# LCD.net
KiCad netlist of a schematic drawn in Altium Designer
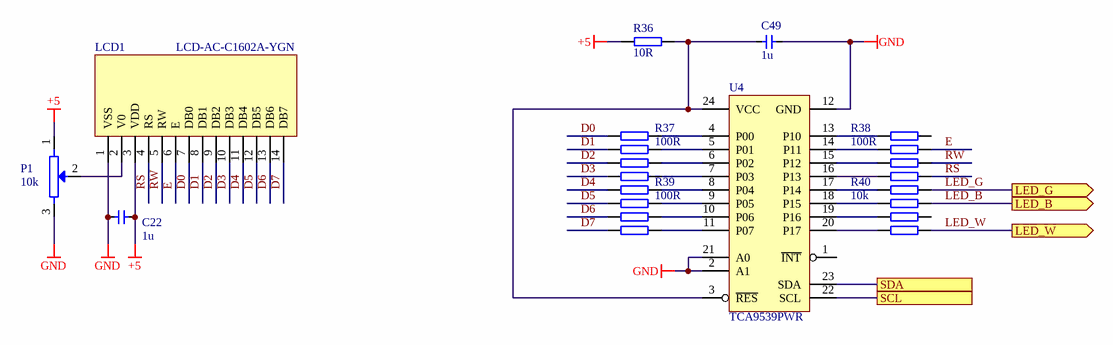
[diagram p0: LCD.SchDoc]

(export (version "E")
  (design (tool "Eeschema 10.0.6"))
  (components
    (comp (ref "C22")
      (value "1u")
      (footprint "C0805")
      (description "C; capacitor")
      (libsource (lib "SONEL_all") (part "C"))
    )
    (comp (ref "C49")
      (value "1u")
      (footprint "C0805")
      (description "C; capacitor")
      (libsource (lib "SONEL_all") (part "C"))
    )
    (comp (ref "LCD1")
      (value "LCD-AC-C1602A-YGN")
      (footprint "LCD-AC-C1602A-YGN")
      (libsource (lib "sch") (part "LCD-AC-C1602A-YGN"))
    )
    (comp (ref "P1")
      (value "10k")
      (footprint "POT67Y")
      (description "R_P")
      (libsource (lib "SONEL_all") (part "POT67Y"))
    )
    (comp (ref "R36")
      (value "10R")
      (footprint "R0805")
      (description "R; resistor")
      (libsource (lib "SONEL_all") (part "R"))
    )
    (comp (ref "R37")
      (value "100R")
      (footprint "YC164")
      (description "R; Drabinka rezystorowa")
      (libsource (lib "SONEL_all") (part "YC164"))
    )
    (comp (ref "R38")
      (value "100R")
      (footprint "YC164")
      (description "R; Drabinka rezystorowa")
      (libsource (lib "SONEL_all") (part "YC164"))
    )
    (comp (ref "R39")
      (value "100R")
      (footprint "YC164")
      (description "R; Drabinka rezystorowa")
      (libsource (lib "SONEL_all") (part "YC164"))
    )
    (comp (ref "R40")
      (value "10k")
      (footprint "YC164")
      (description "R; Drabinka rezystorowa")
      (libsource (lib "SONEL_all") (part "YC164"))
    )
    (comp (ref "U4")
      (value "TCA9539PWR")
      (footprint "PW_R-PDSO-G24")
      (description "I2C 16-BIT port")
      (libsource (lib "SONEL_all") (part "TCA9539PWR"))
    )
  )
  (nets
    (net (code "1") (name "+5") (class "Default")
      (node (ref "C22") (pin "1") (pintype "passive"))
      (node (ref "LCD1") (pin "3") (pinfunction "VDD_3") (pintype "passive"))
      (node (ref "P1") (pin "1") (pinfunction "1_1") (pintype "passive"))
      (node (ref "R36") (pin "2") (pintype "passive"))
    )
    (net (code "2") (name "/D0") (class "Default")
      (node (ref "LCD1") (pin "7") (pinfunction "DB0_7") (pintype "passive"))
      (node (ref "R37") (pin "4") (pintype "passive"))
    )
    (net (code "3") (name "/D1") (class "Default")
      (node (ref "LCD1") (pin "8") (pinfunction "DB1_8") (pintype "passive"))
      (node (ref "R37") (pin "3") (pintype "passive"))
    )
    (net (code "4") (name "/D2") (class "Default")
      (node (ref "LCD1") (pin "9") (pinfunction "DB2_9") (pintype "passive"))
      (node (ref "R37") (pin "2") (pinfunction "2_2") (pintype "passive"))
    )
    (net (code "5") (name "/D3") (class "Default")
      (node (ref "LCD1") (pin "10") (pinfunction "DB3_10") (pintype "passive"))
      (node (ref "R37") (pin "1") (pinfunction "1_1") (pintype "passive"))
    )
    (net (code "6") (name "/D4") (class "Default")
      (node (ref "LCD1") (pin "11") (pinfunction "DB4_11") (pintype "passive"))
      (node (ref "R39") (pin "4") (pintype "passive"))
    )
    (net (code "7") (name "/D5") (class "Default")
      (node (ref "LCD1") (pin "12") (pinfunction "DB5_12") (pintype "passive"))
      (node (ref "R39") (pin "3") (pintype "passive"))
    )
    (net (code "8") (name "/D6") (class "Default")
      (node (ref "LCD1") (pin "13") (pinfunction "DB6_13") (pintype "passive"))
      (node (ref "R39") (pin "2") (pinfunction "2_2") (pintype "passive"))
    )
    (net (code "9") (name "/D7") (class "Default")
      (node (ref "LCD1") (pin "14") (pinfunction "DB7_14") (pintype "passive"))
      (node (ref "R39") (pin "1") (pinfunction "1_1") (pintype "passive"))
    )
    (net (code "10") (name "/E") (class "Default")
      (node (ref "LCD1") (pin "6") (pinfunction "E_6") (pintype "passive"))
      (node (ref "R38") (pin "6") (pintype "passive"))
    )
    (net (code "11") (name "/LED_B") (class "Default") (node (ref "R40") (pin "6") (pintype "passive")))
    (net (code "12") (name "/LED_G") (class "Default") (node (ref "R40") (pin "5") (pintype "passive")))
    (net (code "13") (name "/LED_W") (class "Default") (node (ref "R40") (pin "8") (pintype "passive")))
    (net (code "14") (name "/RS") (class "Default")
      (node (ref "LCD1") (pin "4") (pinfunction "RS_4") (pintype "passive"))
      (node (ref "R38") (pin "8") (pintype "passive"))
    )
    (net (code "15") (name "/RW") (class "Default")
      (node (ref "LCD1") (pin "5") (pinfunction "RW_5") (pintype "passive"))
      (node (ref "R38") (pin "7") (pintype "passive"))
    )
    (net (code "16") (name "/SCL") (class "Default")
      (node (ref "U4") (pin "22") (pinfunction "SCL_22") (pintype "open_collector"))
    )
    (net (code "17") (name "/SDA") (class "Default")
      (node (ref "U4") (pin "23") (pinfunction "SDA_23") (pintype "open_collector"))
    )
    (net (code "18") (name "GND") (class "Default")
      (node (ref "C22") (pin "2") (pintype "passive"))
      (node (ref "C49") (pin "1") (pintype "passive"))
      (node (ref "LCD1") (pin "1") (pinfunction "VSS_1") (pintype "passive"))
      (node (ref "P1") (pin "3") (pinfunction "3_3") (pintype "passive"))
      (node (ref "U4") (pin "12") (pinfunction "GND_12") (pintype "power_in"))
      (node (ref "U4") (pin "2") (pinfunction "A1_2") (pintype "passive"))
      (node (ref "U4") (pin "21") (pinfunction "A0_21") (pintype "passive"))
    )
    (net (code "19") (name "Net-(LCD1-V0)") (class "Default")
      (node (ref "LCD1") (pin "2") (pinfunction "V0_2") (pintype "passive"))
      (node (ref "P1") (pin "2") (pinfunction "2_2") (pintype "passive"))
    )
    (net (code "20") (name "Net-(U4-P00)") (class "Default")
      (node (ref "R37") (pin "5") (pintype "passive"))
      (node (ref "U4") (pin "4") (pinfunction "P00_4") (pintype "passive"))
    )
    (net (code "21") (name "Net-(U4-P01)") (class "Default")
      (node (ref "R37") (pin "6") (pintype "passive"))
      (node (ref "U4") (pin "5") (pinfunction "P01_5") (pintype "passive"))
    )
    (net (code "22") (name "Net-(U4-P02)") (class "Default")
      (node (ref "R37") (pin "7") (pintype "passive"))
      (node (ref "U4") (pin "6") (pinfunction "P02_6") (pintype "passive"))
    )
    (net (code "23") (name "Net-(U4-P03)") (class "Default")
      (node (ref "R37") (pin "8") (pintype "passive"))
      (node (ref "U4") (pin "7") (pinfunction "P03_7") (pintype "passive"))
    )
    (net (code "24") (name "Net-(U4-P04)") (class "Default")
      (node (ref "R39") (pin "5") (pintype "passive"))
      (node (ref "U4") (pin "8") (pinfunction "P04_8") (pintype "passive"))
    )
    (net (code "25") (name "Net-(U4-P05)") (class "Default")
      (node (ref "R39") (pin "6") (pintype "passive"))
      (node (ref "U4") (pin "9") (pinfunction "P05_9") (pintype "passive"))
    )
    (net (code "26") (name "Net-(U4-P06)") (class "Default")
      (node (ref "R39") (pin "7") (pintype "passive"))
      (node (ref "U4") (pin "10") (pinfunction "P06_10") (pintype "passive"))
    )
    (net (code "27") (name "Net-(U4-P07)") (class "Default")
      (node (ref "R39") (pin "8") (pintype "passive"))
      (node (ref "U4") (pin "11") (pinfunction "P07_11") (pintype "passive"))
    )
    (net (code "28") (name "Net-(U4-P10)") (class "Default")
      (node (ref "R38") (pin "4") (pintype "passive"))
      (node (ref "U4") (pin "13") (pinfunction "P10_13") (pintype "passive"))
    )
    (net (code "29") (name "Net-(U4-P11)") (class "Default")
      (node (ref "R38") (pin "3") (pintype "passive"))
      (node (ref "U4") (pin "14") (pinfunction "P11_14") (pintype "passive"))
    )
    (net (code "30") (name "Net-(U4-P12)") (class "Default")
      (node (ref "R38") (pin "2") (pinfunction "2_2") (pintype "passive"))
      (node (ref "U4") (pin "15") (pinfunction "P12_15") (pintype "passive"))
    )
    (net (code "31") (name "Net-(U4-P13)") (class "Default")
      (node (ref "R38") (pin "1") (pinfunction "1_1") (pintype "passive"))
      (node (ref "U4") (pin "16") (pinfunction "P13_16") (pintype "passive"))
    )
    (net (code "32") (name "Net-(U4-P14)") (class "Default")
      (node (ref "R40") (pin "4") (pintype "passive"))
      (node (ref "U4") (pin "17") (pinfunction "P14_17") (pintype "passive"))
    )
    (net (code "33") (name "Net-(U4-P15)") (class "Default")
      (node (ref "R40") (pin "3") (pintype "passive"))
      (node (ref "U4") (pin "18") (pinfunction "P15_18") (pintype "passive"))
    )
    (net (code "34") (name "Net-(U4-P16)") (class "Default")
      (node (ref "R40") (pin "2") (pinfunction "2_2") (pintype "passive"))
      (node (ref "U4") (pin "19") (pinfunction "P16_19") (pintype "passive"))
    )
    (net (code "35") (name "Net-(U4-P17)") (class "Default")
      (node (ref "R40") (pin "1") (pinfunction "1_1") (pintype "passive"))
      (node (ref "U4") (pin "20") (pinfunction "P17_20") (pintype "passive"))
    )
    (net (code "36") (name "Net-(U4-VCC)") (class "Default")
      (node (ref "C49") (pin "2") (pintype "passive"))
      (node (ref "R36") (pin "1") (pintype "passive"))
      (node (ref "U4") (pin "24") (pinfunction "VCC_24") (pintype "power_in"))
      (node (ref "U4") (pin "3") (pinfunction "~{RES}_3") (pintype "passive"))
    )
    (net (code "37") (name "unconnected-(R38-Pad5)") (class "Default")
      (node (ref "R38") (pin "5") (pintype "passive"))
    )
    (net (code "38") (name "unconnected-(R40-Pad7)") (class "Default")
      (node (ref "R40") (pin "7") (pintype "passive"))
    )
    (net (code "39") (name "unconnected-(U4-~{INT}-Pad1)") (class "Default")
      (node (ref "U4") (pin "1") (pinfunction "~{INT}_1") (pintype "open_collector"))
    )
  )
)
